# CoProcessorSP20.net
KiCad netlist of a schematic drawn in EAGLE
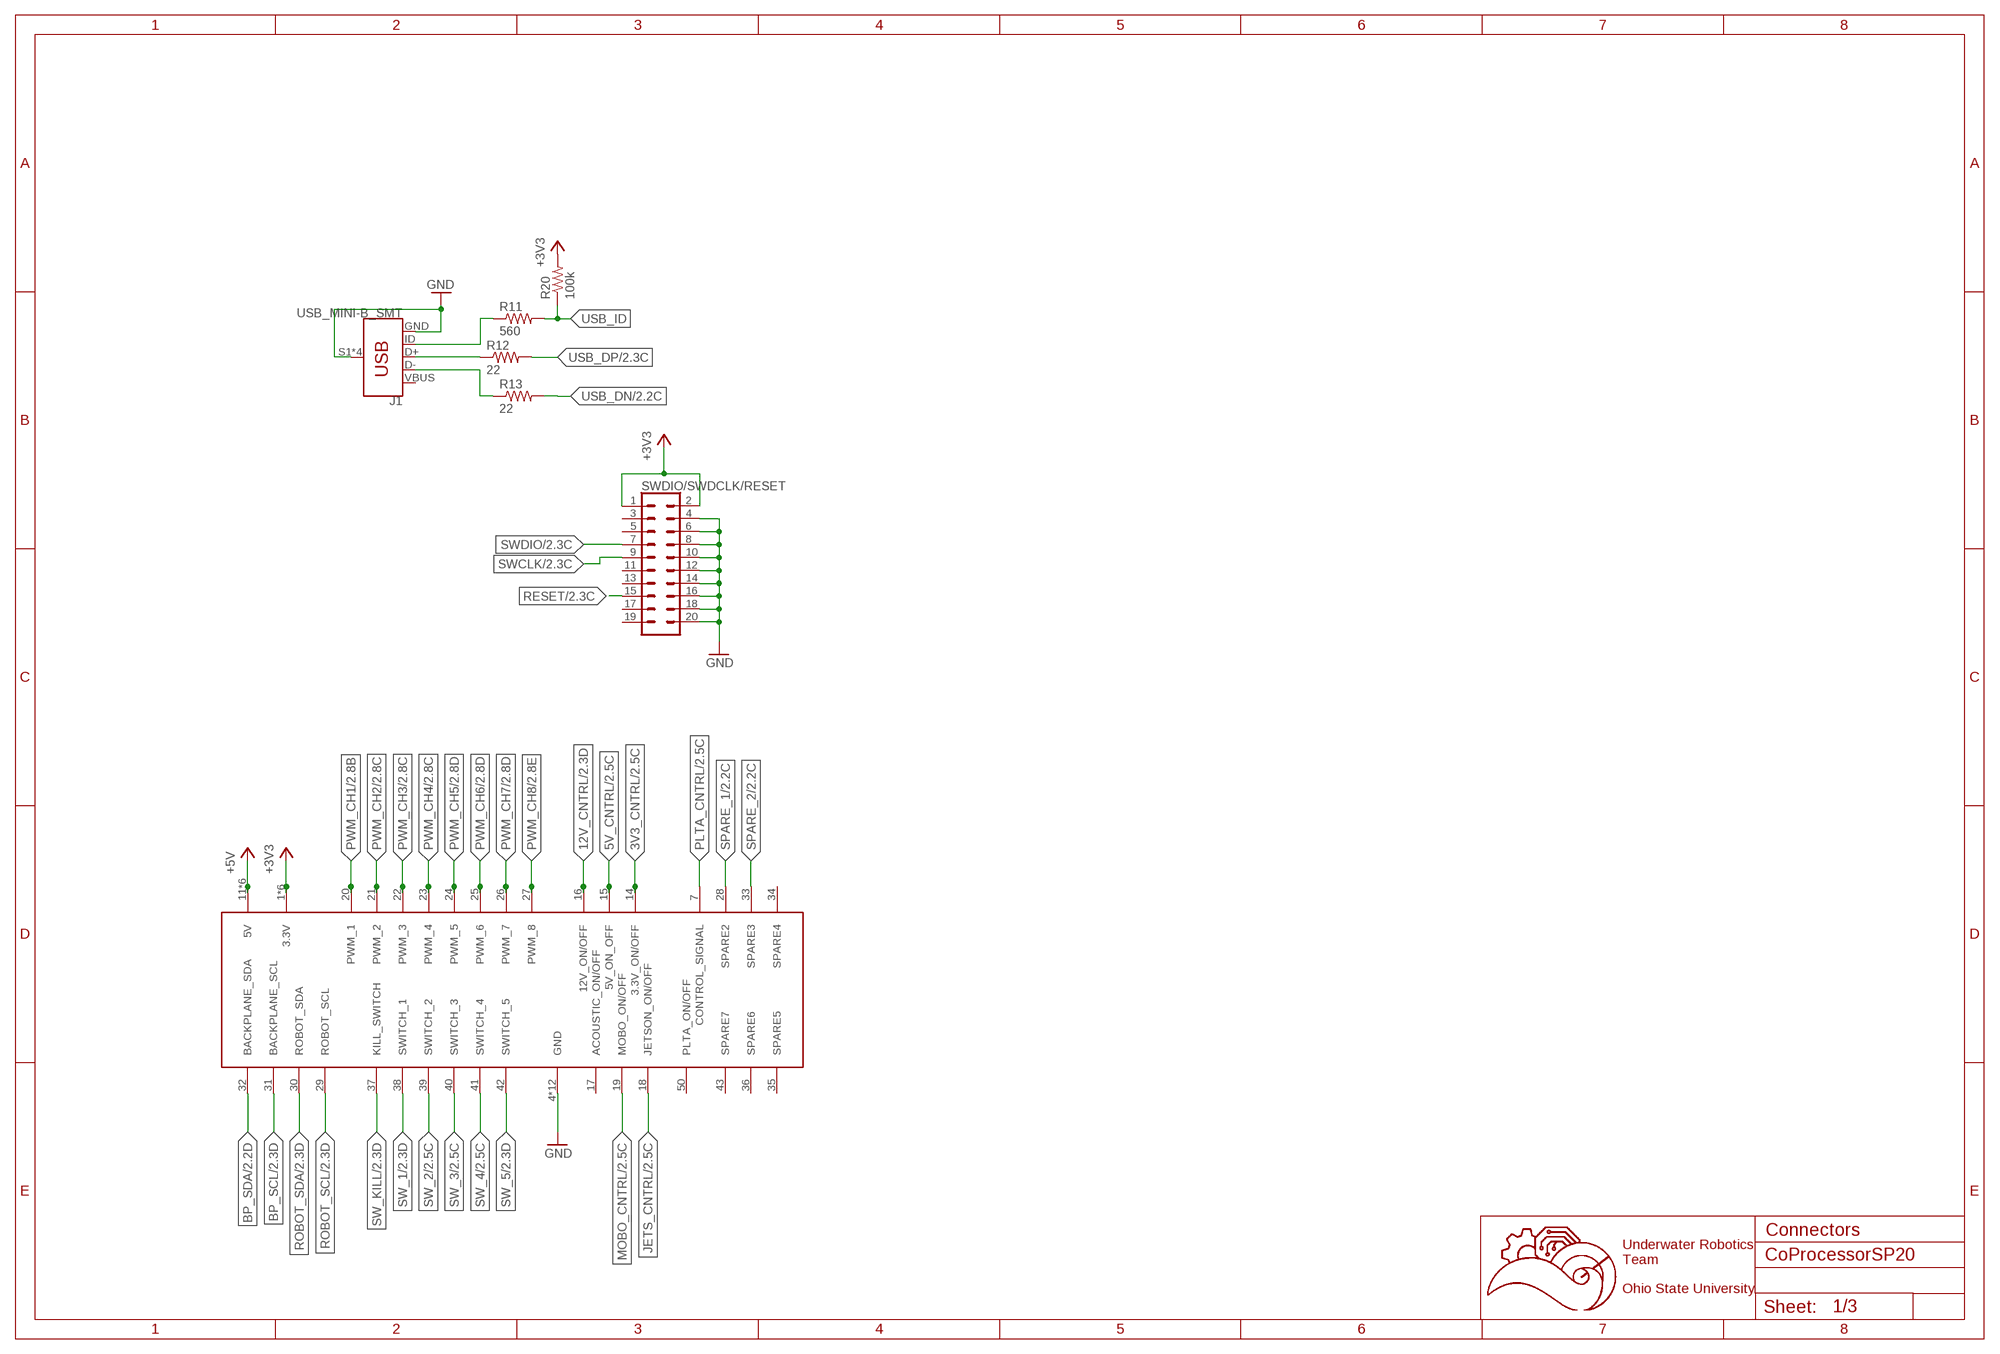
[diagram p0: schematic, sheet 1]
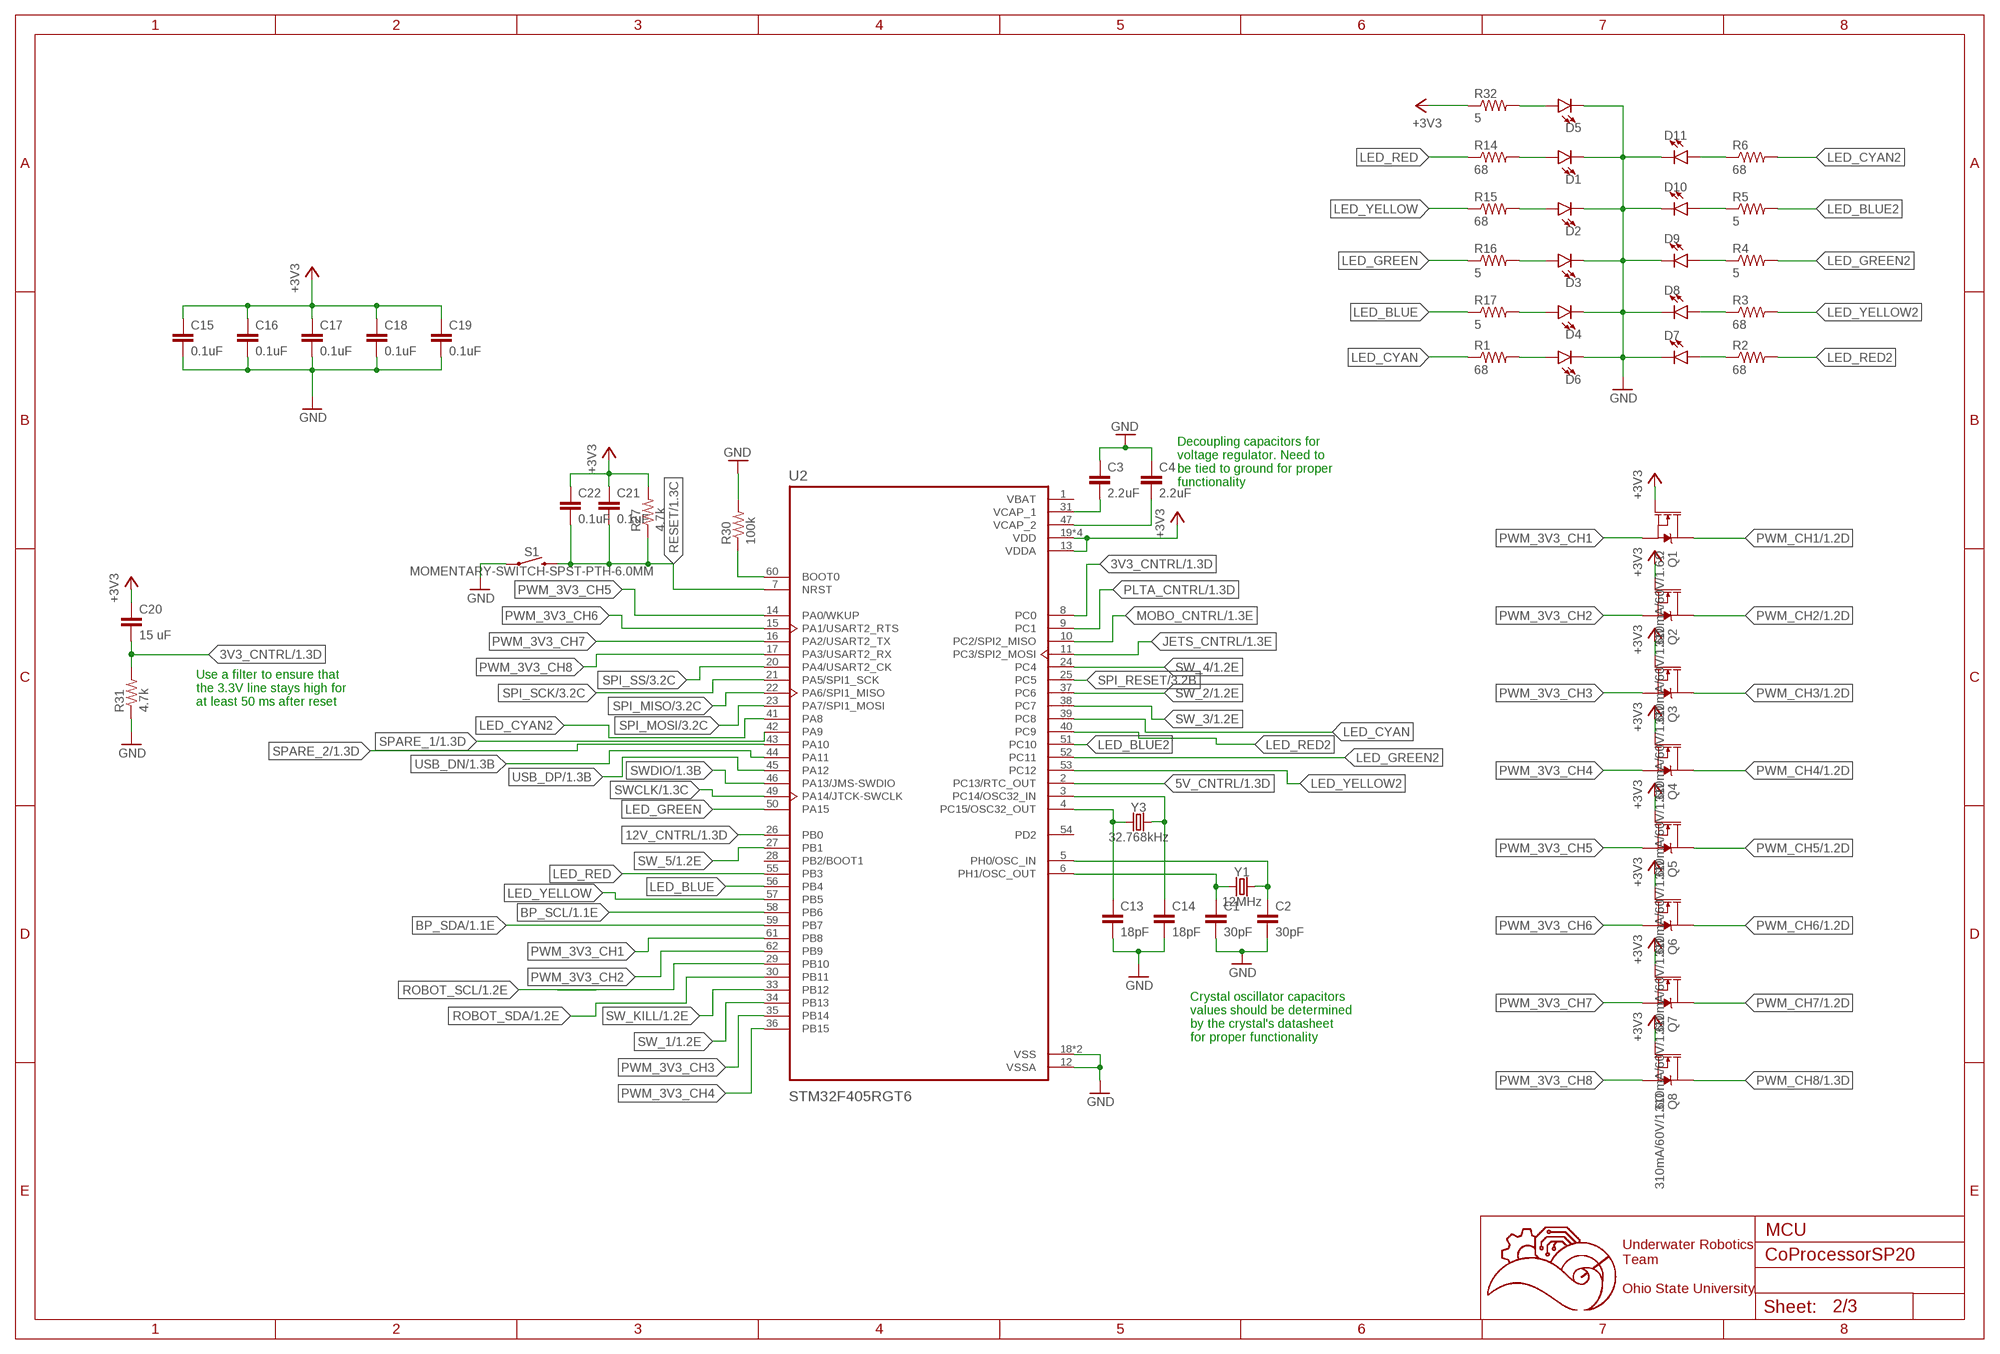
[diagram p1: schematic, sheet 2]
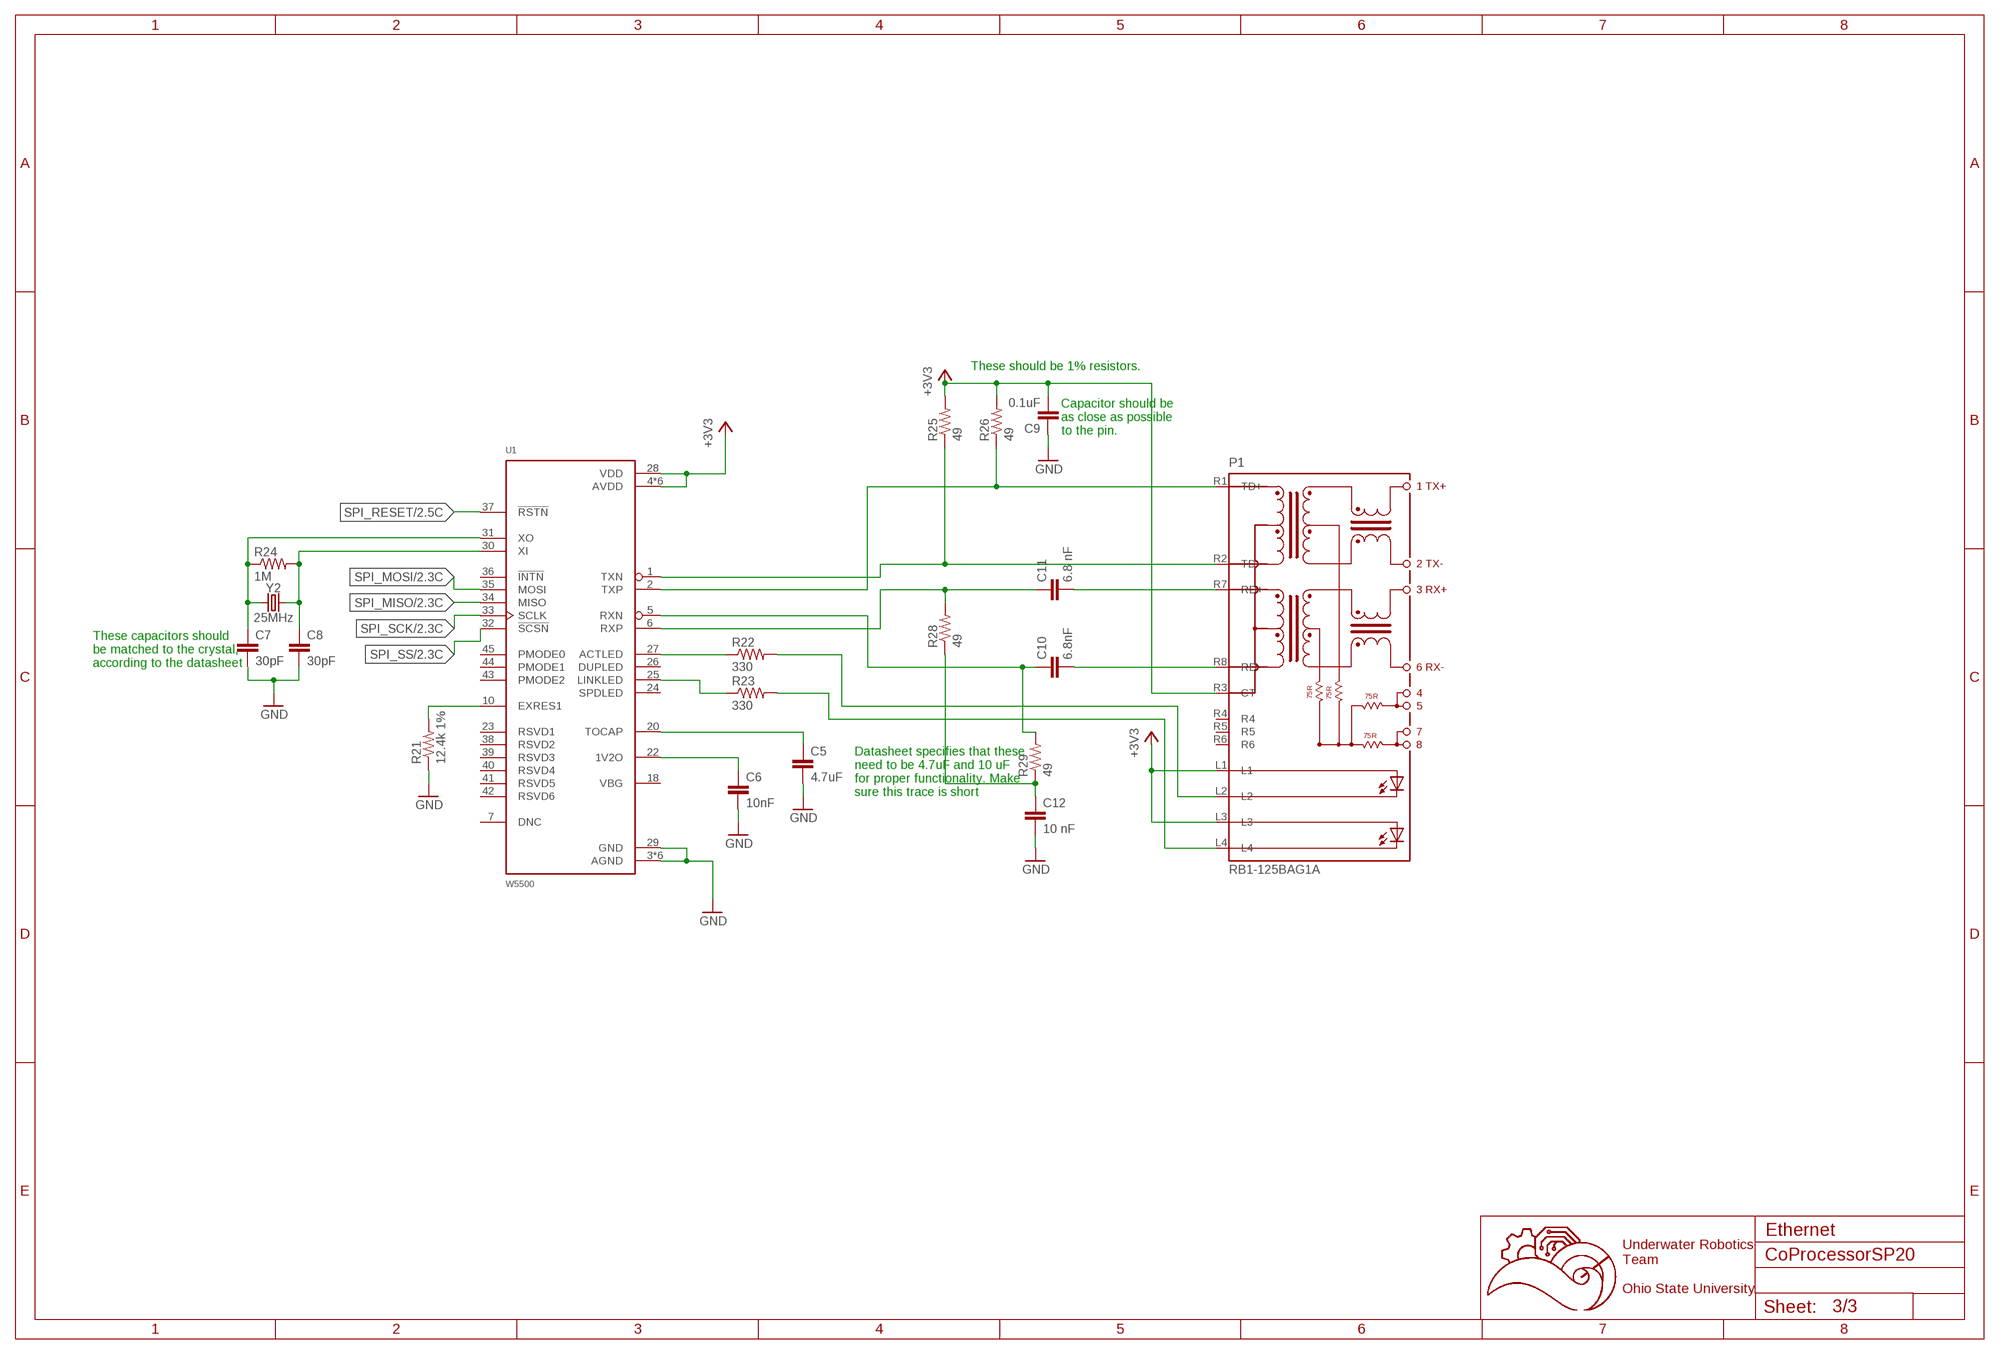
[diagram p2: schematic, sheet 3]

(export (version "E")
  (design (tool "Eeschema 10.0.6"))
  (components
    (comp (ref "C5")
      (value "4.7uF")
      (footprint "eagle-import:C0603")
      (libsource (lib "eagle-import") (part "C-EUC0603"))
    )
    (comp (ref "C6")
      (value "10nF")
      (footprint "eagle-import:C0603")
      (libsource (lib "eagle-import") (part "C-EUC0603"))
    )
    (comp (ref "C7")
      (value "30pF")
      (footprint "eagle-import:C0603")
      (libsource (lib "eagle-import") (part "C-EUC0603"))
    )
    (comp (ref "C8")
      (value "30pF")
      (footprint "eagle-import:C0603")
      (libsource (lib "eagle-import") (part "C-EUC0603"))
    )
    (comp (ref "C9")
      (value "0.1uF")
      (footprint "eagle-import:C0603")
      (libsource (lib "eagle-import") (part "C-EUC0603"))
    )
    (comp (ref "C10")
      (value "6.8nF")
      (footprint "eagle-import:C0603")
      (libsource (lib "eagle-import") (part "C-EUC0603"))
    )
    (comp (ref "C11")
      (value "6.8 nF")
      (footprint "eagle-import:C0603")
      (libsource (lib "eagle-import") (part "C-EUC0603"))
    )
    (comp (ref "C12")
      (value "10 nF")
      (footprint "eagle-import:C0603")
      (libsource (lib "eagle-import") (part "C-EUC0603"))
    )
    (comp (ref "P1")
      (value "RB1-125BAG1A")
      (footprint "eagle-import:WIZNET_RB1-125BAG1A")
      (fields (field (name "MF") "WIZnet"))
      (libsource (lib "eagle-import") (part "RB1-125BAG1A"))
    )
    (comp (ref "R21")
      (value "12.4k 1%")
      (footprint "eagle-import:R0603")
      (libsource (lib "eagle-import") (part "R-US_R0603"))
    )
    (comp (ref "R22")
      (value "330")
      (footprint "eagle-import:R0603")
      (libsource (lib "eagle-import") (part "R-US_R0603"))
    )
    (comp (ref "R23")
      (value "330")
      (footprint "eagle-import:R0603")
      (libsource (lib "eagle-import") (part "R-US_R0603"))
    )
    (comp (ref "R24")
      (value "1M")
      (footprint "eagle-import:R0603")
      (libsource (lib "eagle-import") (part "R-US_R0603"))
    )
    (comp (ref "R25")
      (value "49")
      (footprint "eagle-import:R0603")
      (libsource (lib "eagle-import") (part "R-US_R0603"))
    )
    (comp (ref "R26")
      (value "49")
      (footprint "eagle-import:R0603")
      (libsource (lib "eagle-import") (part "R-US_R0603"))
    )
    (comp (ref "R28")
      (value "49")
      (footprint "eagle-import:R0603")
      (libsource (lib "eagle-import") (part "R-US_R0603"))
    )
    (comp (ref "R29")
      (value "49")
      (footprint "eagle-import:R0603")
      (libsource (lib "eagle-import") (part "R-US_R0603"))
    )
    (comp (ref "U1")
      (value "W5500")
      (footprint "eagle-import:QFP50P900X900X160-48N")
      (fields (field (name "MF") "WIZnet"))
      (libsource (lib "eagle-import") (part "W5500"))
    )
    (comp (ref "Y2")
      (value "25MHz")
      (footprint "eagle-import:HC49US")
      (libsource (lib "eagle-import") (part "CRYSTALPTH-HC49US"))
    )
    (comp (ref "J1")
      (value "USB_MINI-B_SMT")
      (footprint "eagle-import:USB-MINIB")
      (libsource (lib "eagle-import") (part "USB_MINI-B_SMT"))
    )
    (comp (ref "R11")
      (value "560")
      (footprint "eagle-import:R0603")
      (libsource (lib "eagle-import") (part "R-US_R0603"))
    )
    (comp (ref "R12")
      (value "22")
      (footprint "eagle-import:R0603")
      (libsource (lib "eagle-import") (part "R-US_R0603"))
    )
    (comp (ref "R13")
      (value "22")
      (footprint "eagle-import:R0603")
      (libsource (lib "eagle-import") (part "R-US_R0603"))
    )
    (comp (ref "R20")
      (value "100k")
      (footprint "eagle-import:R0603")
      (libsource (lib "eagle-import") (part "R-US_R0603"))
    )
    (comp (ref "SWDIO/SWDCLK/RESET")
      (value "CONN_10X2")
      (footprint "eagle-import:2X10")
      (libsource (lib "eagle-import") (part "CONN_10X2"))
    )
    (comp (ref "U$1")
      (value "5530843-EDGE")
      (footprint "eagle-import:5530843-6-BOARDFINGERS")
      (libsource (lib "eagle-import") (part "5530843-EDGE"))
    )
    (comp (ref "C1")
      (value "30pF")
      (footprint "eagle-import:C0603")
      (libsource (lib "eagle-import") (part "C-EUC0603"))
    )
    (comp (ref "C2")
      (value "30pF")
      (footprint "eagle-import:C0603")
      (libsource (lib "eagle-import") (part "C-EUC0603"))
    )
    (comp (ref "C3")
      (value "2.2uF")
      (footprint "eagle-import:C0603")
      (libsource (lib "eagle-import") (part "C-EUC0603"))
    )
    (comp (ref "C4")
      (value "2.2uF")
      (footprint "eagle-import:C0603")
      (libsource (lib "eagle-import") (part "C-EUC0603"))
    )
    (comp (ref "C13")
      (value "18pF")
      (footprint "eagle-import:C0603")
      (libsource (lib "eagle-import") (part "C-EUC0603"))
    )
    (comp (ref "C14")
      (value "18pF")
      (footprint "eagle-import:C0603")
      (libsource (lib "eagle-import") (part "C-EUC0603"))
    )
    (comp (ref "C15")
      (value "0.1uF")
      (footprint "eagle-import:C0603")
      (libsource (lib "eagle-import") (part "C-EUC0603"))
    )
    (comp (ref "C16")
      (value "0.1uF")
      (footprint "eagle-import:C0603")
      (libsource (lib "eagle-import") (part "C-EUC0603"))
    )
    (comp (ref "C17")
      (value "0.1uF")
      (footprint "eagle-import:C0603")
      (libsource (lib "eagle-import") (part "C-EUC0603"))
    )
    (comp (ref "C18")
      (value "0.1uF")
      (footprint "eagle-import:C0603")
      (libsource (lib "eagle-import") (part "C-EUC0603"))
    )
    (comp (ref "C19")
      (value "0.1uF")
      (footprint "eagle-import:C0603")
      (libsource (lib "eagle-import") (part "C-EUC0603"))
    )
    (comp (ref "C20")
      (value "15 uF")
      (footprint "eagle-import:C050-025X075")
      (libsource (lib "eagle-import") (part "C-EU050-025X075"))
    )
    (comp (ref "C21")
      (value "0.1uF")
      (footprint "eagle-import:C0603")
      (libsource (lib "eagle-import") (part "C-EUC0603"))
    )
    (comp (ref "C22")
      (value "0.1uF")
      (footprint "eagle-import:C0603")
      (libsource (lib "eagle-import") (part "C-EUC0603"))
    )
    (comp (ref "D1")
      (value "LED0603")
      (footprint "eagle-import:LED-0603")
      (libsource (lib "eagle-import") (part "LED0603"))
    )
    (comp (ref "D2")
      (value "LED0603")
      (footprint "eagle-import:LED-0603")
      (libsource (lib "eagle-import") (part "LED0603"))
    )
    (comp (ref "D3")
      (value "LED0603")
      (footprint "eagle-import:LED-0603")
      (libsource (lib "eagle-import") (part "LED0603"))
    )
    (comp (ref "D4")
      (value "LED0603")
      (footprint "eagle-import:LED-0603")
      (libsource (lib "eagle-import") (part "LED0603"))
    )
    (comp (ref "D5")
      (value "LED0603")
      (footprint "eagle-import:LED-0603")
      (libsource (lib "eagle-import") (part "LED0603"))
    )
    (comp (ref "D6")
      (value "LED0603")
      (footprint "eagle-import:LED-0603")
      (libsource (lib "eagle-import") (part "LED0603"))
    )
    (comp (ref "D7")
      (value "LED0603")
      (footprint "eagle-import:LED-0603")
      (libsource (lib "eagle-import") (part "LED0603"))
    )
    (comp (ref "D8")
      (value "LED0603")
      (footprint "eagle-import:LED-0603")
      (libsource (lib "eagle-import") (part "LED0603"))
    )
    (comp (ref "D9")
      (value "LED0603")
      (footprint "eagle-import:LED-0603")
      (libsource (lib "eagle-import") (part "LED0603"))
    )
    (comp (ref "D10")
      (value "LED0603")
      (footprint "eagle-import:LED-0603")
      (libsource (lib "eagle-import") (part "LED0603"))
    )
    (comp (ref "D11")
      (value "LED0603")
      (footprint "eagle-import:LED-0603")
      (libsource (lib "eagle-import") (part "LED0603"))
    )
    (comp (ref "Q1")
      (value "310mA/60V/1.6Ω")
      (footprint "eagle-import:SOT323")
      (libsource (lib "eagle-import") (part "MOSFET-NCH-2N7002PW"))
    )
    (comp (ref "Q2")
      (value "310mA/60V/1.6Ω")
      (footprint "eagle-import:SOT323")
      (libsource (lib "eagle-import") (part "MOSFET-NCH-2N7002PW"))
    )
    (comp (ref "Q3")
      (value "310mA/60V/1.6Ω")
      (footprint "eagle-import:SOT323")
      (libsource (lib "eagle-import") (part "MOSFET-NCH-2N7002PW"))
    )
    (comp (ref "Q4")
      (value "310mA/60V/1.6Ω")
      (footprint "eagle-import:SOT323")
      (libsource (lib "eagle-import") (part "MOSFET-NCH-2N7002PW"))
    )
    (comp (ref "Q5")
      (value "310mA/60V/1.6Ω")
      (footprint "eagle-import:SOT323")
      (libsource (lib "eagle-import") (part "MOSFET-NCH-2N7002PW"))
    )
    (comp (ref "Q6")
      (value "310mA/60V/1.6Ω")
      (footprint "eagle-import:SOT323")
      (libsource (lib "eagle-import") (part "MOSFET-NCH-2N7002PW"))
    )
    (comp (ref "Q7")
      (value "310mA/60V/1.6Ω")
      (footprint "eagle-import:SOT323")
      (libsource (lib "eagle-import") (part "MOSFET-NCH-2N7002PW"))
    )
    (comp (ref "Q8")
      (value "310mA/60V/1.6Ω")
      (footprint "eagle-import:SOT323")
      (libsource (lib "eagle-import") (part "MOSFET-NCH-2N7002PW"))
    )
    (comp (ref "R1")
      (value "68")
      (footprint "eagle-import:R0603")
      (libsource (lib "eagle-import") (part "R-US_R0603"))
    )
    (comp (ref "R2")
      (value "68")
      (footprint "eagle-import:R0603")
      (libsource (lib "eagle-import") (part "R-US_R0603"))
    )
    (comp (ref "R3")
      (value "68")
      (footprint "eagle-import:R0603")
      (libsource (lib "eagle-import") (part "R-US_R0603"))
    )
    (comp (ref "R4")
      (value "5")
      (footprint "eagle-import:R0603")
      (libsource (lib "eagle-import") (part "R-US_R0603"))
    )
    (comp (ref "R5")
      (value "5")
      (footprint "eagle-import:R0603")
      (libsource (lib "eagle-import") (part "R-US_R0603"))
    )
    (comp (ref "R6")
      (value "68")
      (footprint "eagle-import:R0603")
      (libsource (lib "eagle-import") (part "R-US_R0603"))
    )
    (comp (ref "R14")
      (value "68")
      (footprint "eagle-import:R0603")
      (libsource (lib "eagle-import") (part "R-US_R0603"))
    )
    (comp (ref "R15")
      (value "68")
      (footprint "eagle-import:R0603")
      (libsource (lib "eagle-import") (part "R-US_R0603"))
    )
    (comp (ref "R16")
      (value "5")
      (footprint "eagle-import:R0603")
      (libsource (lib "eagle-import") (part "R-US_R0603"))
    )
    (comp (ref "R17")
      (value "5")
      (footprint "eagle-import:R0603")
      (libsource (lib "eagle-import") (part "R-US_R0603"))
    )
    (comp (ref "R27")
      (value "4.7k")
      (footprint "eagle-import:R0603")
      (libsource (lib "eagle-import") (part "R-US_R0603"))
    )
    (comp (ref "R30")
      (value "100k")
      (footprint "eagle-import:R0603")
      (libsource (lib "eagle-import") (part "R-US_R0603"))
    )
    (comp (ref "R31")
      (value "4.7k")
      (footprint "eagle-import:R0603")
      (libsource (lib "eagle-import") (part "R-US_R0603"))
    )
    (comp (ref "R32")
      (value "5")
      (footprint "eagle-import:R0603")
      (libsource (lib "eagle-import") (part "R-US_R0603"))
    )
    (comp (ref "S1")
      (value "MOMENTARY-SWITCH-SPST-PTH-6.0MM")
      (footprint "eagle-import:TACTILE_SWITCH_PTH_6.0MM")
      (libsource (lib "eagle-import") (part "MOMENTARY-SWITCH-SPST-PTH-6.0MM"))
    )
    (comp (ref "U2")
      (value "STM32F405RGT6")
      (footprint "eagle-import:QFP50P1200X1200X160-64N")
      (fields (field (name "MF") "STMicroelectronics"))
      (libsource (lib "eagle-import") (part "STM32F405RGT6"))
    )
    (comp (ref "Y1")
      (value "12MHz")
      (footprint "eagle-import:HC49US")
      (libsource (lib "eagle-import") (part "CRYSTAL-16MHZPTH-HC49US"))
    )
    (comp (ref "Y3")
      (value "32.768kHz")
      (footprint "eagle-import:CRYSTAL-SMD-3.2X1.5MM")
      (libsource (lib "eagle-import") (part "CRYSTAL-32.768KHZSMD-3.2X1.5"))
    )
  )
  (nets
    (net (code "1") (name "+3V3") (class "Default")
      (node (ref "C15") (pin "1") (pinfunction "1_1") (pintype "passive"))
      (node (ref "C16") (pin "1") (pinfunction "1_1") (pintype "passive"))
      (node (ref "C17") (pin "1") (pinfunction "1_1") (pintype "passive"))
      (node (ref "C18") (pin "1") (pinfunction "1_1") (pintype "passive"))
      (node (ref "C19") (pin "1") (pinfunction "1_1") (pintype "passive"))
      (node (ref "C20") (pin "1") (pinfunction "1_1") (pintype "passive"))
      (node (ref "C21") (pin "1") (pinfunction "1_1") (pintype "passive"))
      (node (ref "C22") (pin "1") (pinfunction "1_1") (pintype "passive"))
      (node (ref "C9") (pin "2") (pinfunction "2_2") (pintype "passive"))
      (node (ref "P1") (pin "L1") (pinfunction "L1_L1") (pintype "passive"))
      (node (ref "P1") (pin "L3") (pinfunction "L3_L3") (pintype "passive"))
      (node (ref "P1") (pin "R3") (pinfunction "CT_R3") (pintype "input"))
      (node (ref "Q1") (pin "1") (pinfunction "G_1") (pintype "bidirectional"))
      (node (ref "Q2") (pin "1") (pinfunction "G_1") (pintype "bidirectional"))
      (node (ref "Q3") (pin "1") (pinfunction "G_1") (pintype "bidirectional"))
      (node (ref "Q4") (pin "1") (pinfunction "G_1") (pintype "bidirectional"))
      (node (ref "Q5") (pin "1") (pinfunction "G_1") (pintype "bidirectional"))
      (node (ref "Q6") (pin "1") (pinfunction "G_1") (pintype "bidirectional"))
      (node (ref "Q7") (pin "1") (pinfunction "G_1") (pintype "bidirectional"))
      (node (ref "Q8") (pin "1") (pinfunction "G_1") (pintype "bidirectional"))
      (node (ref "R20") (pin "2") (pinfunction "2_2") (pintype "passive"))
      (node (ref "R25") (pin "2") (pinfunction "2_2") (pintype "passive"))
      (node (ref "R26") (pin "2") (pinfunction "2_2") (pintype "passive"))
      (node (ref "R27") (pin "2") (pinfunction "2_2") (pintype "passive"))
      (node (ref "R32") (pin "1") (pinfunction "1_1") (pintype "passive"))
      (node (ref "SWDIO/SWDCLK/RESET") (pin "1") (pinfunction "1_1") (pintype "passive"))
      (node (ref "SWDIO/SWDCLK/RESET") (pin "2") (pinfunction "2_2") (pintype "passive"))
      (node (ref "U$1") (pin "1") (pinfunction "3.3V_1") (pintype "bidirectional"))
      (node (ref "U$1") (pin "2") (pinfunction "3.3V_2") (pintype "bidirectional"))
      (node (ref "U$1") (pin "3") (pinfunction "3.3V_3") (pintype "bidirectional"))
      (node (ref "U$1") (pin "54") (pinfunction "3.3V_54") (pintype "bidirectional"))
      (node (ref "U$1") (pin "55") (pinfunction "3.3V_55") (pintype "bidirectional"))
      (node (ref "U$1") (pin "56") (pinfunction "3.3V_56") (pintype "bidirectional"))
      (node (ref "U1") (pin "11") (pinfunction "AVDD_11") (pintype "power_in"))
      (node (ref "U1") (pin "15") (pinfunction "AVDD_15") (pintype "power_in"))
      (node (ref "U1") (pin "17") (pinfunction "AVDD_17") (pintype "power_in"))
      (node (ref "U1") (pin "21") (pinfunction "AVDD_21") (pintype "power_in"))
      (node (ref "U1") (pin "28") (pinfunction "VDD_28") (pintype "power_in"))
      (node (ref "U1") (pin "4") (pinfunction "AVDD_4") (pintype "power_in"))
      (node (ref "U1") (pin "8") (pinfunction "AVDD_8") (pintype "power_in"))
      (node (ref "U2") (pin "13") (pinfunction "VDDA_13") (pintype "power_in"))
      (node (ref "U2") (pin "19") (pinfunction "VDD_19") (pintype "power_in"))
      (node (ref "U2") (pin "32") (pinfunction "VDD_32") (pintype "power_in"))
      (node (ref "U2") (pin "48") (pinfunction "VDD_48") (pintype "power_in"))
      (node (ref "U2") (pin "64") (pinfunction "VDD_64") (pintype "power_in"))
    )
    (net (code "2") (name "+5V") (class "Default")
      (node (ref "U$1") (pin "11") (pinfunction "5V_11") (pintype "bidirectional"))
      (node (ref "U$1") (pin "12") (pinfunction "5V_12") (pintype "bidirectional"))
      (node (ref "U$1") (pin "13") (pinfunction "5V_13") (pintype "bidirectional"))
      (node (ref "U$1") (pin "44") (pinfunction "5V_44") (pintype "bidirectional"))
      (node (ref "U$1") (pin "45") (pinfunction "5V_45") (pintype "bidirectional"))
      (node (ref "U$1") (pin "46") (pinfunction "5V_46") (pintype "bidirectional"))
    )
    (net (code "3") (name "3V3_CNTRL") (class "Default")
      (node (ref "C20") (pin "2") (pinfunction "2_2") (pintype "passive"))
      (node (ref "R31") (pin "2") (pinfunction "2_2") (pintype "passive"))
      (node (ref "U$1") (pin "14") (pinfunction "3.3V_ON/OFF_14") (pintype "bidirectional"))
      (node (ref "U2") (pin "8") (pinfunction "PC0_8") (pintype "bidirectional"))
    )
    (net (code "4") (name "5V_CNTRL") (class "Default")
      (node (ref "U$1") (pin "15") (pinfunction "5V_ON_OFF_15") (pintype "bidirectional"))
      (node (ref "U2") (pin "2") (pinfunction "PC13/RTC_OUT_2") (pintype "bidirectional"))
    )
    (net (code "5") (name "12V_CNTRL") (class "Default")
      (node (ref "U$1") (pin "16") (pinfunction "12V_ON/OFF_16") (pintype "bidirectional"))
      (node (ref "U2") (pin "26") (pinfunction "PB0_26") (pintype "bidirectional"))
    )
    (net (code "6") (name "BP_SCL") (class "Default")
      (node (ref "U$1") (pin "31") (pinfunction "BACKPLANE_SCL_31") (pintype "bidirectional"))
      (node (ref "U2") (pin "58") (pinfunction "PB6_58") (pintype "bidirectional"))
    )
    (net (code "7") (name "BP_SDA") (class "Default")
      (node (ref "U$1") (pin "32") (pinfunction "BACKPLANE_SDA_32") (pintype "bidirectional"))
      (node (ref "U2") (pin "59") (pinfunction "PB7_59") (pintype "bidirectional"))
    )
    (net (code "8") (name "GND") (class "Default")
      (node (ref "C1") (pin "2") (pinfunction "2_2") (pintype "passive"))
      (node (ref "C12") (pin "2") (pinfunction "2_2") (pintype "passive"))
      (node (ref "C13") (pin "2") (pinfunction "2_2") (pintype "passive"))
      (node (ref "C14") (pin "2") (pinfunction "2_2") (pintype "passive"))
      (node (ref "C15") (pin "2") (pinfunction "2_2") (pintype "passive"))
      (node (ref "C16") (pin "2") (pinfunction "2_2") (pintype "passive"))
      (node (ref "C17") (pin "2") (pinfunction "2_2") (pintype "passive"))
      (node (ref "C18") (pin "2") (pinfunction "2_2") (pintype "passive"))
      (node (ref "C19") (pin "2") (pinfunction "2_2") (pintype "passive"))
      (node (ref "C2") (pin "2") (pinfunction "2_2") (pintype "passive"))
      (node (ref "C3") (pin "1") (pinfunction "1_1") (pintype "passive"))
      (node (ref "C4") (pin "1") (pinfunction "1_1") (pintype "passive"))
      (node (ref "C5") (pin "2") (pinfunction "2_2") (pintype "passive"))
      (node (ref "C6") (pin "2") (pinfunction "2_2") (pintype "passive"))
      (node (ref "C7") (pin "2") (pinfunction "2_2") (pintype "passive"))
      (node (ref "C8") (pin "2") (pinfunction "2_2") (pintype "passive"))
      (node (ref "C9") (pin "1") (pinfunction "1_1") (pintype "passive"))
      (node (ref "D1") (pin "C") (pinfunction "C_C") (pintype "passive"))
      (node (ref "D10") (pin "C") (pinfunction "C_C") (pintype "passive"))
      (node (ref "D11") (pin "C") (pinfunction "C_C") (pintype "passive"))
      (node (ref "D2") (pin "C") (pinfunction "C_C") (pintype "passive"))
      (node (ref "D3") (pin "C") (pinfunction "C_C") (pintype "passive"))
      (node (ref "D4") (pin "C") (pinfunction "C_C") (pintype "passive"))
      (node (ref "D5") (pin "C") (pinfunction "C_C") (pintype "passive"))
      (node (ref "D6") (pin "C") (pinfunction "C_C") (pintype "passive"))
      (node (ref "D7") (pin "C") (pinfunction "C_C") (pintype "passive"))
      (node (ref "D8") (pin "C") (pinfunction "C_C") (pintype "passive"))
      (node (ref "D9") (pin "C") (pinfunction "C_C") (pintype "passive"))
      (node (ref "J1") (pin "GND") (pinfunction "GND_GND") (pintype "power_in"))
      (node (ref "J1") (pin "S1") (pinfunction "SHIELD_S1") (pintype "bidirectional"))
      (node (ref "J1") (pin "S2") (pinfunction "SHIELD_S2") (pintype "bidirectional"))
      (node (ref "J1") (pin "S3") (pinfunction "SHIELD_S3") (pintype "bidirectional"))
      (node (ref "J1") (pin "S4") (pinfunction "SHIELD_S4") (pintype "bidirectional"))
      (node (ref "R21") (pin "1") (pinfunction "1_1") (pintype "passive"))
      (node (ref "R30") (pin "2") (pinfunction "2_2") (pintype "passive"))
      (node (ref "R31") (pin "1") (pinfunction "1_1") (pintype "passive"))
      (node (ref "S1") (pin "1") (pinfunction "1_1") (pintype "passive"))
      (node (ref "SWDIO/SWDCLK/RESET") (pin "10") (pinfunction "10_10") (pintype "passive"))
      (node (ref "SWDIO/SWDCLK/RESET") (pin "12") (pinfunction "12_12") (pintype "passive"))
      (node (ref "SWDIO/SWDCLK/RESET") (pin "14") (pinfunction "14_14") (pintype "passive"))
      (node (ref "SWDIO/SWDCLK/RESET") (pin "16") (pinfunction "16_16") (pintype "passive"))
      (node (ref "SWDIO/SWDCLK/RESET") (pin "18") (pinfunction "18_18") (pintype "passive"))
      (node (ref "SWDIO/SWDCLK/RESET") (pin "20") (pinfunction "20_20") (pintype "passive"))
      (node (ref "SWDIO/SWDCLK/RESET") (pin "4") (pinfunction "4_4") (pintype "passive"))
      (node (ref "SWDIO/SWDCLK/RESET") (pin "6") (pinfunction "6_6") (pintype "passive"))
      (node (ref "SWDIO/SWDCLK/RESET") (pin "8") (pinfunction "8_8") (pintype "passive"))
      (node (ref "U$1") (pin "10") (pinfunction "GND_10") (pintype "bidirectional"))
      (node (ref "U$1") (pin "4") (pinfunction "GND_4") (pintype "bidirectional"))
      (node (ref "U$1") (pin "47") (pinfunction "GND_47") (pintype "bidirectional"))
      (node (ref "U$1") (pin "48") (pinfunction "GND_48") (pintype "bidirectional"))
      (node (ref "U$1") (pin "49") (pinfunction "GND_49") (pintype "bidirectional"))
      (node (ref "U$1") (pin "5") (pinfunction "GND_5") (pintype "bidirectional"))
      (node (ref "U$1") (pin "51") (pinfunction "GND_51") (pintype "bidirectional"))
      (node (ref "U$1") (pin "52") (pinfunction "GND_52") (pintype "bidirectional"))
      (node (ref "U$1") (pin "53") (pinfunction "GND_53") (pintype "bidirectional"))
      (node (ref "U$1") (pin "6") (pinfunction "GND_6") (pintype "bidirectional"))
      (node (ref "U$1") (pin "8") (pinfunction "GND_8") (pintype "bidirectional"))
      (node (ref "U$1") (pin "9") (pinfunction "GND_9") (pintype "bidirectional"))
      (node (ref "U1") (pin "14") (pinfunction "AGND_14") (pintype "power_in"))
      (node (ref "U1") (pin "16") (pinfunction "AGND_16") (pintype "power_in"))
      (node (ref "U1") (pin "19") (pinfunction "AGND_19") (pintype "power_in"))
      (node (ref "U1") (pin "29") (pinfunction "GND_29") (pintype "passive"))
      (node (ref "U1") (pin "3") (pinfunction "AGND_3") (pintype "power_in"))
      (node (ref "U1") (pin "48") (pinfunction "AGND_48") (pintype "power_in"))
      (node (ref "U1") (pin "9") (pinfunction "AGND_9") (pintype "power_in"))
      (node (ref "U2") (pin "12") (pinfunction "VSSA_12") (pintype "power_in"))
      (node (ref "U2") (pin "18") (pinfunction "VSS_18") (pintype "power_in"))
      (node (ref "U2") (pin "63") (pinfunction "VSS_63") (pintype "power_in"))
    )
    (net (code "9") (name "JETS_CNTRL") (class "Default")
      (node (ref "U$1") (pin "18") (pinfunction "JETSON_ON/OFF_18") (pintype "bidirectional"))
      (node (ref "U2") (pin "11") (pinfunction "PC3/SPI2_MOSI_11") (pintype "bidirectional"))
    )
    (net (code "10") (name "LED_BLUE") (class "Default")
      (node (ref "R17") (pin "1") (pinfunction "1_1") (pintype "passive"))
      (node (ref "U2") (pin "56") (pinfunction "PB4_56") (pintype "bidirectional"))
    )
    (net (code "11") (name "LED_BLUE2") (class "Default")
      (node (ref "R5") (pin "2") (pinfunction "2_2") (pintype "passive"))
      (node (ref "U2") (pin "51") (pinfunction "PC10_51") (pintype "bidirectional"))
    )
    (net (code "12") (name "LED_CYAN") (class "Default")
      (node (ref "R1") (pin "1") (pinfunction "1_1") (pintype "passive"))
      (node (ref "U2") (pin "39") (pinfunction "PC8_39") (pintype "bidirectional"))
    )
    (net (code "13") (name "LED_CYAN2") (class "Default")
      (node (ref "R6") (pin "2") (pinfunction "2_2") (pintype "passive"))
      (node (ref "U2") (pin "41") (pinfunction "PA8_41") (pintype "bidirectional"))
    )
    (net (code "14") (name "LED_GREEN") (class "Default")
      (node (ref "R16") (pin "1") (pinfunction "1_1") (pintype "passive"))
      (node (ref "U2") (pin "50") (pinfunction "PA15_50") (pintype "bidirectional"))
    )
    (net (code "15") (name "LED_GREEN2") (class "Default")
      (node (ref "R4") (pin "2") (pinfunction "2_2") (pintype "passive"))
      (node (ref "U2") (pin "52") (pinfunction "PC11_52") (pintype "bidirectional"))
    )
    (net (code "16") (name "LED_RED") (class "Default")
      (node (ref "R14") (pin "1") (pinfunction "1_1") (pintype "passive"))
      (node (ref "U2") (pin "55") (pinfunction "PB3_55") (pintype "bidirectional"))
    )
    (net (code "17") (name "LED_RED2") (class "Default")
      (node (ref "R2") (pin "2") (pinfunction "2_2") (pintype "passive"))
      (node (ref "U2") (pin "40") (pinfunction "PC9_40") (pintype "bidirectional"))
    )
    (net (code "18") (name "LED_YELLOW") (class "Default")
      (node (ref "R15") (pin "1") (pinfunction "1_1") (pintype "passive"))
      (node (ref "U2") (pin "57") (pinfunction "PB5_57") (pintype "bidirectional"))
    )
    (net (code "19") (name "LED_YELLOW2") (class "Default")
      (node (ref "R3") (pin "2") (pinfunction "2_2") (pintype "passive"))
      (node (ref "U2") (pin "53") (pinfunction "PC12_53") (pintype "bidirectional"))
    )
    (net (code "20") (name "MOBO_CNTRL") (class "Default")
      (node (ref "U$1") (pin "19") (pinfunction "MOBO_ON/OFF_19") (pintype "bidirectional"))
      (node (ref "U2") (pin "10") (pinfunction "PC2/SPI2_MISO_10") (pintype "bidirectional"))
    )
    (net (code "21") (name "Net-(C12-Pad1)") (class "Default")
      (node (ref "C12") (pin "1") (pinfunction "1_1") (pintype "passive"))
      (node (ref "R28") (pin "1") (pinfunction "1_1") (pintype "passive"))
      (node (ref "R29") (pin "1") (pinfunction "1_1") (pintype "passive"))
    )
    (net (code "22") (name "Net-(D1-PadA)") (class "Default")
      (node (ref "D1") (pin "A") (pinfunction "A_A") (pintype "passive"))
      (node (ref "R14") (pin "2") (pinfunction "2_2") (pintype "passive"))
    )
    (net (code "23") (name "Net-(D2-PadA)") (class "Default")
      (node (ref "D2") (pin "A") (pinfunction "A_A") (pintype "passive"))
      (node (ref "R15") (pin "2") (pinfunction "2_2") (pintype "passive"))
    )
    (net (code "24") (name "Net-(D3-PadA)") (class "Default")
      (node (ref "D3") (pin "A") (pinfunction "A_A") (pintype "passive"))
      (node (ref "R16") (pin "2") (pinfunction "2_2") (pintype "passive"))
    )
    (net (code "25") (name "Net-(D4-PadA)") (class "Default")
      (node (ref "D4") (pin "A") (pinfunction "A_A") (pintype "passive"))
      (node (ref "R17") (pin "2") (pinfunction "2_2") (pintype "passive"))
    )
    (net (code "26") (name "Net-(D5-PadA)") (class "Default")
      (node (ref "D5") (pin "A") (pinfunction "A_A") (pintype "passive"))
      (node (ref "R32") (pin "2") (pinfunction "2_2") (pintype "passive"))
    )
    (net (code "27") (name "Net-(D6-PadA)") (class "Default")
      (node (ref "D6") (pin "A") (pinfunction "A_A") (pintype "passive"))
      (node (ref "R1") (pin "2") (pinfunction "2_2") (pintype "passive"))
    )
    (net (code "28") (name "Net-(D7-PadA)") (class "Default")
      (node (ref "D7") (pin "A") (pinfunction "A_A") (pintype "passive"))
      (node (ref "R2") (pin "1") (pinfunction "1_1") (pintype "passive"))
    )
    (net (code "29") (name "Net-(D8-PadA)") (class "Default")
      (node (ref "D8") (pin "A") (pinfunction "A_A") (pintype "passive"))
      (node (ref "R3") (pin "1") (pinfunction "1_1") (pintype "passive"))
    )
    (net (code "30") (name "Net-(D9-PadA)") (class "Default")
      (node (ref "D9") (pin "A") (pinfunction "A_A") (pintype "passive"))
      (node (ref "R4") (pin "1") (pinfunction "1_1") (pintype "passive"))
    )
    (net (code "31") (name "Net-(D10-PadA)") (class "Default")
      (node (ref "D10") (pin "A") (pinfunction "A_A") (pintype "passive"))
      (node (ref "R5") (pin "1") (pinfunction "1_1") (pintype "passive"))
    )
    (net (code "32") (name "Net-(D11-PadA)") (class "Default")
      (node (ref "D11") (pin "A") (pinfunction "A_A") (pintype "passive"))
      (node (ref "R6") (pin "1") (pinfunction "1_1") (pintype "passive"))
    )
    (net (code "33") (name "Net-(J1-PadD+)") (class "Default")
      (node (ref "J1") (pin "D+") (pinfunction "D+_D+") (pintype "bidirectional"))
      (node (ref "R12") (pin "1") (pinfunction "1_1") (pintype "passive"))
    )
    (net (code "34") (name "Net-(J1-PadD-)") (class "Default")
      (node (ref "J1") (pin "D-") (pinfunction "D-_D-") (pintype "bidirectional"))
      (node (ref "R13") (pin "1") (pinfunction "1_1") (pintype "passive"))
    )
    (net (code "35") (name "Net-(J1-PadID)") (class "Default")
      (node (ref "J1") (pin "ID") (pinfunction "ID_ID") (pintype "bidirectional"))
      (node (ref "R11") (pin "1") (pinfunction "1_1") (pintype "passive"))
    )
    (net (code "36") (name "Net-(P1-PadL2)") (class "Default")
      (node (ref "P1") (pin "L2") (pinfunction "L2_L2") (pintype "passive"))
      (node (ref "R22") (pin "2") (pinfunction "2_2") (pintype "passive"))
    )
    (net (code "37") (name "Net-(P1-PadL4)") (class "Default")
      (node (ref "P1") (pin "L4") (pinfunction "L4_L4") (pintype "passive"))
      (node (ref "R23") (pin "2") (pinfunction "2_2") (pintype "passive"))
    )
    (net (code "38") (name "Net-(P1-RD+)") (class "Default")
      (node (ref "C11") (pin "2") (pinfunction "2_2") (pintype "passive"))
      (node (ref "P1") (pin "R7") (pinfunction "RD+_R7") (pintype "input"))
    )
    (net (code "39") (name "Net-(P1-RD-)") (class "Default")
      (node (ref "C10") (pin "2") (pinfunction "2_2") (pintype "passive"))
      (node (ref "P1") (pin "R8") (pinfunction "RD-_R8") (pintype "input"))
    )
    (net (code "40") (name "Net-(P1-TD+)") (class "Default")
      (node (ref "P1") (pin "R1") (pinfunction "TD+_R1") (pintype "input"))
      (node (ref "R26") (pin "1") (pinfunction "1_1") (pintype "passive"))
      (node (ref "U1") (pin "2") (pinfunction "TXP_2") (pintype "output"))
    )
    (net (code "41") (name "Net-(P1-TD-)") (class "Default")
      (node (ref "P1") (pin "R2") (pinfunction "TD-_R2") (pintype "input"))
      (node (ref "R25") (pin "1") (pinfunction "1_1") (pintype "passive"))
      (node (ref "U1") (pin "1") (pinfunction "TXN_1") (pintype "output"))
    )
    (net (code "42") (name "Net-(U1-1V2O)") (class "Default")
      (node (ref "C6") (pin "1") (pinfunction "1_1") (pintype "passive"))
      (node (ref "U1") (pin "22") (pinfunction "1V2O_22") (pintype "output"))
    )
    (net (code "43") (name "Net-(U1-ACTLED)") (class "Default")
      (node (ref "R22") (pin "1") (pinfunction "1_1") (pintype "passive"))
      (node (ref "U1") (pin "27") (pinfunction "ACTLED_27") (pintype "output"))
    )
    (net (code "44") (name "Net-(U1-EXRES1)") (class "Default")
      (node (ref "R21") (pin "2") (pinfunction "2_2") (pintype "passive"))
      (node (ref "U1") (pin "10") (pinfunction "EXRES1_10") (pintype "bidirectional"))
    )
    (net (code "45") (name "Net-(U1-LINKLED)") (class "Default")
      (node (ref "R23") (pin "1") (pinfunction "1_1") (pintype "passive"))
      (node (ref "U1") (pin "25") (pinfunction "LINKLED_25") (pintype "output"))
    )
    (net (code "46") (name "Net-(U1-RXN)") (class "Default")
      (node (ref "C10") (pin "1") (pinfunction "1_1") (pintype "passive"))
      (node (ref "R29") (pin "2") (pinfunction "2_2") (pintype "passive"))
      (node (ref "U1") (pin "5") (pinfunction "RXN_5") (pintype "input"))
    )
    (net (code "47") (name "Net-(U1-RXP)") (class "Default")
      (node (ref "C11") (pin "1") (pinfunction "1_1") (pintype "passive"))
      (node (ref "R28") (pin "2") (pinfunction "2_2") (pintype "passive"))
      (node (ref "U1") (pin "6") (pinfunction "RXP_6") (pintype "input"))
    )
    (net (code "48") (name "Net-(U1-TOCAP)") (class "Default")
      (node (ref "C5") (pin "1") (pinfunction "1_1") (pintype "passive"))
      (node (ref "U1") (pin "20") (pinfunction "TOCAP_20") (pintype "output"))
    )
    (net (code "49") (name "Net-(U1-XI)") (class "Default")
      (node (ref "C8") (pin "1") (pinfunction "1_1") (pintype "passive"))
      (node (ref "R24") (pin "2") (pinfunction "2_2") (pintype "passive"))
      (node (ref "U1") (pin "30") (pinfunction "XI_30") (pintype "input"))
      (node (ref "Y2") (pin "2") (pinfunction "2_2") (pintype "passive"))
    )
    (net (code "50") (name "Net-(U1-XO)") (class "Default")
      (node (ref "C7") (pin "1") (pinfunction "1_1") (pintype "passive"))
      (node (ref "R24") (pin "1") (pinfunction "1_1") (pintype "passive"))
      (node (ref "U1") (pin "31") (pinfunction "XO_31") (pintype "output"))
      (node (ref "Y2") (pin "1") (pinfunction "1_1") (pintype "passive"))
    )
    (net (code "51") (name "Net-(U2-BOOT0)") (class "Default")
      (node (ref "R30") (pin "1") (pinfunction "1_1") (pintype "passive"))
      (node (ref "U2") (pin "60") (pinfunction "BOOT0_60") (pintype "bidirectional"))
    )
    (net (code "52") (name "Net-(U2-PC14{slash}OSC32_IN)") (class "Default")
      (node (ref "C14") (pin "1") (pinfunction "1_1") (pintype "passive"))
      (node (ref "U2") (pin "3") (pinfunction "PC14/OSC32_IN_3") (pintype "bidirectional"))
      (node (ref "Y3") (pin "P$2") (pinfunction "2_P$2") (pintype "passive"))
    )
    (net (code "53") (name "Net-(U2-PC15{slash}OSC32_OUT)") (class "Default")
      (node (ref "C13") (pin "1") (pinfunction "1_1") (pintype "passive"))
      (node (ref "U2") (pin "4") (pinfunction "PC15/OSC32_OUT_4") (pintype "bidirectional"))
      (node (ref "Y3") (pin "P$1") (pinfunction "1_P$1") (pintype "passive"))
    )
    (net (code "54") (name "Net-(U2-PH0{slash}OSC_IN)") (class "Default")
      (node (ref "C2") (pin "1") (pinfunction "1_1") (pintype "passive"))
      (node (ref "U2") (pin "5") (pinfunction "PH0/OSC_IN_5") (pintype "bidirectional"))
      (node (ref "Y1") (pin "2") (pinfunction "2_2") (pintype "passive"))
    )
    (net (code "55") (name "Net-(U2-PH1{slash}OSC_OUT)") (class "Default")
      (node (ref "C1") (pin "1") (pinfunction "1_1") (pintype "passive"))
      (node (ref "U2") (pin "6") (pinfunction "PH1/OSC_OUT_6") (pintype "bidirectional"))
      (node (ref "Y1") (pin "1") (pinfunction "1_1") (pintype "passive"))
    )
    (net (code "56") (name "Net-(U2-VCAP_1)") (class "Default")
      (node (ref "C3") (pin "2") (pinfunction "2_2") (pintype "passive"))
      (node (ref "U2") (pin "31") (pinfunction "VCAP_1_31") (pintype "power_in"))
    )
    (net (code "57") (name "Net-(U2-VCAP_2)") (class "Default")
      (node (ref "C4") (pin "2") (pinfunction "2_2") (pintype "passive"))
      (node (ref "U2") (pin "47") (pinfunction "VCAP_2_47") (pintype "power_in"))
    )
    (net (code "58") (name "PLTA_CNTRL") (class "Default")
      (node (ref "U$1") (pin "7") (pinfunction "CONTROL_SIGNAL_7") (pintype "bidirectional"))
      (node (ref "U2") (pin "9") (pinfunction "PC1_9") (pintype "bidirectional"))
    )
    (net (code "59") (name "PWM_3V3_CH1") (class "Default")
      (node (ref "Q1") (pin "2") (pinfunction "S_2") (pintype "bidirectional"))
      (node (ref "U2") (pin "61") (pinfunction "PB8_61") (pintype "bidirectional"))
    )
    (net (code "60") (name "PWM_3V3_CH2") (class "Default")
      (node (ref "Q2") (pin "2") (pinfunction "S_2") (pintype "bidirectional"))
      (node (ref "U2") (pin "62") (pinfunction "PB9_62") (pintype "bidirectional"))
    )
    (net (code "61") (name "PWM_3V3_CH3") (class "Default")
      (node (ref "Q3") (pin "2") (pinfunction "S_2") (pintype "bidirectional"))
      (node (ref "U2") (pin "35") (pinfunction "PB14_35") (pintype "bidirectional"))
    )
    (net (code "62") (name "PWM_3V3_CH4") (class "Default")
      (node (ref "Q4") (pin "2") (pinfunction "S_2") (pintype "bidirectional"))
      (node (ref "U2") (pin "36") (pinfunction "PB15_36") (pintype "bidirectional"))
    )
    (net (code "63") (name "PWM_3V3_CH5") (class "Default")
      (node (ref "Q5") (pin "2") (pinfunction "S_2") (pintype "bidirectional"))
      (node (ref "U2") (pin "14") (pinfunction "PA0/WKUP_14") (pintype "bidirectional"))
    )
    (net (code "64") (name "PWM_3V3_CH6") (class "Default")
      (node (ref "Q6") (pin "2") (pinfunction "S_2") (pintype "bidirectional"))
      (node (ref "U2") (pin "15") (pinfunction "PA1/USART2_RTS_15") (pintype "bidirectional"))
    )
    (net (code "65") (name "PWM_3V3_CH7") (class "Default")
      (node (ref "Q7") (pin "2") (pinfunction "S_2") (pintype "bidirectional"))
      (node (ref "U2") (pin "16") (pinfunction "PA2/USART2_TX_16") (pintype "bidirectional"))
    )
    (net (code "66") (name "PWM_3V3_CH8") (class "Default")
      (node (ref "Q8") (pin "2") (pinfunction "S_2") (pintype "bidirectional"))
      (node (ref "U2") (pin "17") (pinfunction "PA3/USART2_RX_17") (pintype "bidirectional"))
    )
    (net (code "67") (name "PWM_CH1") (class "Default")
      (node (ref "Q1") (pin "3") (pinfunction "D_3") (pintype "bidirectional"))
      (node (ref "U$1") (pin "20") (pinfunction "PWM_1_20") (pintype "bidirectional"))
    )
    (net (code "68") (name "PWM_CH2") (class "Default")
      (node (ref "Q2") (pin "3") (pinfunction "D_3") (pintype "bidirectional"))
      (node (ref "U$1") (pin "21") (pinfunction "PWM_2_21") (pintype "bidirectional"))
    )
    (net (code "69") (name "PWM_CH3") (class "Default")
      (node (ref "Q3") (pin "3") (pinfunction "D_3") (pintype "bidirectional"))
      (node (ref "U$1") (pin "22") (pinfunction "PWM_3_22") (pintype "bidirectional"))
    )
    (net (code "70") (name "PWM_CH4") (class "Default")
      (node (ref "Q4") (pin "3") (pinfunction "D_3") (pintype "bidirectional"))
      (node (ref "U$1") (pin "23") (pinfunction "PWM_4_23") (pintype "bidirectional"))
    )
    (net (code "71") (name "PWM_CH5") (class "Default")
      (node (ref "Q5") (pin "3") (pinfunction "D_3") (pintype "bidirectional"))
      (node (ref "U$1") (pin "24") (pinfunction "PWM_5_24") (pintype "bidirectional"))
    )
    (net (code "72") (name "PWM_CH6") (class "Default")
      (node (ref "Q6") (pin "3") (pinfunction "D_3") (pintype "bidirectional"))
      (node (ref "U$1") (pin "25") (pinfunction "PWM_6_25") (pintype "bidirectional"))
    )
    (net (code "73") (name "PWM_CH7") (class "Default")
      (node (ref "Q7") (pin "3") (pinfunction "D_3") (pintype "bidirectional"))
      (node (ref "U$1") (pin "26") (pinfunction "PWM_7_26") (pintype "bidirectional"))
    )
    (net (code "74") (name "PWM_CH8") (class "Default")
      (node (ref "Q8") (pin "3") (pinfunction "D_3") (pintype "bidirectional"))
      (node (ref "U$1") (pin "27") (pinfunction "PWM_8_27") (pintype "bidirectional"))
    )
    (net (code "75") (name "RESET") (class "Default")
      (node (ref "C21") (pin "2") (pinfunction "2_2") (pintype "passive"))
      (node (ref "C22") (pin "2") (pinfunction "2_2") (pintype "passive"))
      (node (ref "R27") (pin "1") (pinfunction "1_1") (pintype "passive"))
      (node (ref "S1") (pin "3") (pinfunction "2_3") (pintype "passive"))
      (node (ref "SWDIO/SWDCLK/RESET") (pin "15") (pinfunction "15_15") (pintype "passive"))
      (node (ref "U2") (pin "7") (pinfunction "NRST_7") (pintype "bidirectional"))
    )
    (net (code "76") (name "ROBOT_SCL") (class "Default")
      (node (ref "U$1") (pin "29") (pinfunction "ROBOT_SCL_29") (pintype "bidirectional"))
      (node (ref "U2") (pin "29") (pinfunction "PB10_29") (pintype "bidirectional"))
    )
    (net (code "77") (name "ROBOT_SDA") (class "Default")
      (node (ref "U$1") (pin "30") (pinfunction "ROBOT_SDA_30") (pintype "bidirectional"))
      (node (ref "U2") (pin "30") (pinfunction "PB11_30") (pintype "bidirectional"))
    )
    (net (code "78") (name "SPARE_1") (class "Default")
      (node (ref "U$1") (pin "28") (pinfunction "SPARE2_28") (pintype "bidirectional"))
      (node (ref "U2") (pin "42") (pinfunction "PA9_42") (pintype "bidirectional"))
    )
    (net (code "79") (name "SPARE_2") (class "Default")
      (node (ref "U$1") (pin "33") (pinfunction "SPARE3_33") (pintype "bidirectional"))
      (node (ref "U2") (pin "43") (pinfunction "PA10_43") (pintype "bidirectional"))
    )
    (net (code "80") (name "SPI_MISO") (class "Default")
      (node (ref "U1") (pin "34") (pinfunction "MISO_34") (pintype "output"))
      (node (ref "U2") (pin "22") (pinfunction "PA6/SPI1_MISO_22") (pintype "bidirectional"))
    )
    (net (code "81") (name "SPI_MOSI") (class "Default")
      (node (ref "U1") (pin "35") (pinfunction "MOSI_35") (pintype "input"))
      (node (ref "U2") (pin "23") (pinfunction "PA7/SPI1_MOSI_23") (pintype "bidirectional"))
    )
    (net (code "82") (name "SPI_RESET") (class "Default")
      (node (ref "U1") (pin "37") (pinfunction "~{RSTN}_37") (pintype "input"))
      (node (ref "U2") (pin "25") (pinfunction "PC5_25") (pintype "bidirectional"))
    )
    (net (code "83") (name "SPI_SCK") (class "Default")
      (node (ref "U1") (pin "33") (pinfunction "SCLK_33") (pintype "input"))
      (node (ref "U2") (pin "21") (pinfunction "PA5/SPI1_SCK_21") (pintype "bidirectional"))
    )
    (net (code "84") (name "SPI_SS") (class "Default")
      (node (ref "U1") (pin "32") (pinfunction "~{SCSN}_32") (pintype "input"))
      (node (ref "U2") (pin "20") (pinfunction "PA4/USART2_CK_20") (pintype "bidirectional"))
    )
    (net (code "85") (name "SWCLK") (class "Default")
      (node (ref "SWDIO/SWDCLK/RESET") (pin "9") (pinfunction "9_9") (pintype "passive"))
      (node (ref "U2") (pin "49") (pinfunction "PA14/JTCK-SWCLK_49") (pintype "bidirectional"))
    )
    (net (code "86") (name "SWDIO") (class "Default")
      (node (ref "SWDIO/SWDCLK/RESET") (pin "7") (pinfunction "7_7") (pintype "passive"))
      (node (ref "U2") (pin "46") (pinfunction "PA13/JMS-SWDIO_46") (pintype "bidirectional"))
    )
    (net (code "87") (name "SW_1") (class "Default")
      (node (ref "U$1") (pin "38") (pinfunction "SWITCH_1_38") (pintype "output"))
      (node (ref "U2") (pin "34") (pinfunction "PB13_34") (pintype "bidirectional"))
    )
    (net (code "88") (name "SW_2") (class "Default")
      (node (ref "U$1") (pin "39") (pinfunction "SWITCH_2_39") (pintype "output"))
      (node (ref "U2") (pin "37") (pinfunction "PC6_37") (pintype "bidirectional"))
    )
    (net (code "89") (name "SW_3") (class "Default")
      (node (ref "U$1") (pin "40") (pinfunction "SWITCH_3_40") (pintype "output"))
      (node (ref "U2") (pin "38") (pinfunction "PC7_38") (pintype "bidirectional"))
    )
    (net (code "90") (name "SW_4") (class "Default")
      (node (ref "U$1") (pin "41") (pinfunction "SWITCH_4_41") (pintype "output"))
      (node (ref "U2") (pin "24") (pinfunction "PC4_24") (pintype "bidirectional"))
    )
    (net (code "91") (name "SW_5") (class "Default")
      (node (ref "U$1") (pin "42") (pinfunction "SWITCH_5_42") (pintype "output"))
      (node (ref "U2") (pin "27") (pinfunction "PB1_27") (pintype "bidirectional"))
    )
    (net (code "92") (name "SW_KILL") (class "Default")
      (node (ref "U$1") (pin "37") (pinfunction "KILL_SWITCH_37") (pintype "output"))
      (node (ref "U2") (pin "33") (pinfunction "PB12_33") (pintype "bidirectional"))
    )
    (net (code "93") (name "USB_DN") (class "Default")
      (node (ref "R13") (pin "2") (pinfunction "2_2") (pintype "passive"))
      (node (ref "U2") (pin "44") (pinfunction "PA11_44") (pintype "bidirectional"))
    )
    (net (code "94") (name "USB_DP") (class "Default")
      (node (ref "R12") (pin "2") (pinfunction "2_2") (pintype "passive"))
      (node (ref "U2") (pin "45") (pinfunction "PA12_45") (pintype "bidirectional"))
    )
    (net (code "95") (name "USB_ID") (class "Default")
      (node (ref "R11") (pin "2") (pinfunction "2_2") (pintype "passive"))
      (node (ref "R20") (pin "1") (pinfunction "1_1") (pintype "passive"))
    )
    (net (code "96") (name "VBAT") (class "Default")
      (node (ref "U2") (pin "1") (pinfunction "VBAT_1") (pintype "power_in"))
    )
    (net (code "97") (name "VBUS") (class "Default")
      (node (ref "J1") (pin "VBUS") (pinfunction "VBUS_VBUS") (pintype "power_in"))
    )
    (net (code "98") (name "unconnected-(P1-PadR4)") (class "Default")
      (node (ref "P1") (pin "R4") (pinfunction "R4_R4") (pintype "input"))
    )
    (net (code "99") (name "unconnected-(P1-PadR5)") (class "Default")
      (node (ref "P1") (pin "R5") (pinfunction "R5_R5") (pintype "input"))
    )
    (net (code "100") (name "unconnected-(P1-PadR6)") (class "Default")
      (node (ref "P1") (pin "R6") (pinfunction "R6_R6") (pintype "input"))
    )
    (net (code "101") (name "unconnected-(SWDIO/SWDCLK/RESET-Pad3)") (class "Default")
      (node (ref "SWDIO/SWDCLK/RESET") (pin "3") (pinfunction "3_3") (pintype "passive"))
    )
    (net (code "102") (name "unconnected-(SWDIO/SWDCLK/RESET-Pad5)") (class "Default")
      (node (ref "SWDIO/SWDCLK/RESET") (pin "5") (pinfunction "5_5") (pintype "passive"))
    )
    (net (code "103") (name "unconnected-(SWDIO/SWDCLK/RESET-Pad11)") (class "Default")
      (node (ref "SWDIO/SWDCLK/RESET") (pin "11") (pinfunction "11_11") (pintype "passive"))
    )
    (net (code "104") (name "unconnected-(SWDIO/SWDCLK/RESET-Pad13)") (class "Default")
      (node (ref "SWDIO/SWDCLK/RESET") (pin "13") (pinfunction "13_13") (pintype "passive"))
    )
    (net (code "105") (name "unconnected-(SWDIO/SWDCLK/RESET-Pad17)") (class "Default")
      (node (ref "SWDIO/SWDCLK/RESET") (pin "17") (pinfunction "17_17") (pintype "passive"))
    )
    (net (code "106") (name "unconnected-(SWDIO/SWDCLK/RESET-Pad19)") (class "Default")
      (node (ref "SWDIO/SWDCLK/RESET") (pin "19") (pinfunction "19_19") (pintype "passive"))
    )
    (net (code "107") (name "unconnected-(U$1-ACOUSTIC_ON{slash}OFF-Pad17)") (class "Default")
      (node (ref "U$1") (pin "17") (pinfunction "ACOUSTIC_ON/OFF_17") (pintype "bidirectional"))
    )
    (net (code "108") (name "unconnected-(U$1-PLTA_ON{slash}OFF-Pad50)") (class "Default")
      (node (ref "U$1") (pin "50") (pinfunction "PLTA_ON/OFF_50") (pintype "bidirectional"))
    )
    (net (code "109") (name "unconnected-(U$1-SPARE4-Pad34)") (class "Default")
      (node (ref "U$1") (pin "34") (pinfunction "SPARE4_34") (pintype "bidirectional"))
    )
    (net (code "110") (name "unconnected-(U$1-SPARE5-Pad35)") (class "Default")
      (node (ref "U$1") (pin "35") (pinfunction "SPARE5_35") (pintype "bidirectional"))
    )
    (net (code "111") (name "unconnected-(U$1-SPARE6-Pad36)") (class "Default")
      (node (ref "U$1") (pin "36") (pinfunction "SPARE6_36") (pintype "bidirectional"))
    )
    (net (code "112") (name "unconnected-(U$1-SPARE7-Pad43)") (class "Default")
      (node (ref "U$1") (pin "43") (pinfunction "SPARE7_43") (pintype "bidirectional"))
    )
    (net (code "113") (name "unconnected-(U1-DNC-Pad7)") (class "Default")
      (node (ref "U1") (pin "7") (pinfunction "DNC_7") (pintype "bidirectional"))
    )
    (net (code "114") (name "unconnected-(U1-DUPLED-Pad26)") (class "Default")
      (node (ref "U1") (pin "26") (pinfunction "DUPLED_26") (pintype "output"))
    )
    (net (code "115") (name "unconnected-(U1-PMODE0-Pad45)") (class "Default")
      (node (ref "U1") (pin "45") (pinfunction "PMODE0_45") (pintype "input"))
    )
    (net (code "116") (name "unconnected-(U1-PMODE1-Pad44)") (class "Default")
      (node (ref "U1") (pin "44") (pinfunction "PMODE1_44") (pintype "input"))
    )
    (net (code "117") (name "unconnected-(U1-PMODE2-Pad43)") (class "Default")
      (node (ref "U1") (pin "43") (pinfunction "PMODE2_43") (pintype "input"))
    )
    (net (code "118") (name "unconnected-(U1-RSVD1-Pad23)") (class "Default")
      (node (ref "U1") (pin "23") (pinfunction "RSVD1_23") (pintype "input"))
    )
    (net (code "119") (name "unconnected-(U1-RSVD2-Pad38)") (class "Default")
      (node (ref "U1") (pin "38") (pinfunction "RSVD2_38") (pintype "input"))
    )
    (net (code "120") (name "unconnected-(U1-RSVD3-Pad39)") (class "Default")
      (node (ref "U1") (pin "39") (pinfunction "RSVD3_39") (pintype "input"))
    )
    (net (code "121") (name "unconnected-(U1-RSVD4-Pad40)") (class "Default")
      (node (ref "U1") (pin "40") (pinfunction "RSVD4_40") (pintype "input"))
    )
    (net (code "122") (name "unconnected-(U1-RSVD5-Pad41)") (class "Default")
      (node (ref "U1") (pin "41") (pinfunction "RSVD5_41") (pintype "input"))
    )
    (net (code "123") (name "unconnected-(U1-RSVD6-Pad42)") (class "Default")
      (node (ref "U1") (pin "42") (pinfunction "RSVD6_42") (pintype "input"))
    )
    (net (code "124") (name "unconnected-(U1-SPDLED-Pad24)") (class "Default")
      (node (ref "U1") (pin "24") (pinfunction "SPDLED_24") (pintype "output"))
    )
    (net (code "125") (name "unconnected-(U1-VBG-Pad18)") (class "Default")
      (node (ref "U1") (pin "18") (pinfunction "VBG_18") (pintype "output"))
    )
    (net (code "126") (name "unconnected-(U1-~{INTN}-Pad36)") (class "Default")
      (node (ref "U1") (pin "36") (pinfunction "~{INTN}_36") (pintype "input"))
    )
    (net (code "127") (name "unconnected-(U2-PB2{slash}BOOT1-Pad28)") (class "Default")
      (node (ref "U2") (pin "28") (pinfunction "PB2/BOOT1_28") (pintype "bidirectional"))
    )
    (net (code "128") (name "unconnected-(U2-PD2-Pad54)") (class "Default")
      (node (ref "U2") (pin "54") (pinfunction "PD2_54") (pintype "bidirectional"))
    )
  )
)
